# mcu.net
KiCad netlist of a schematic drawn in Altium Designer
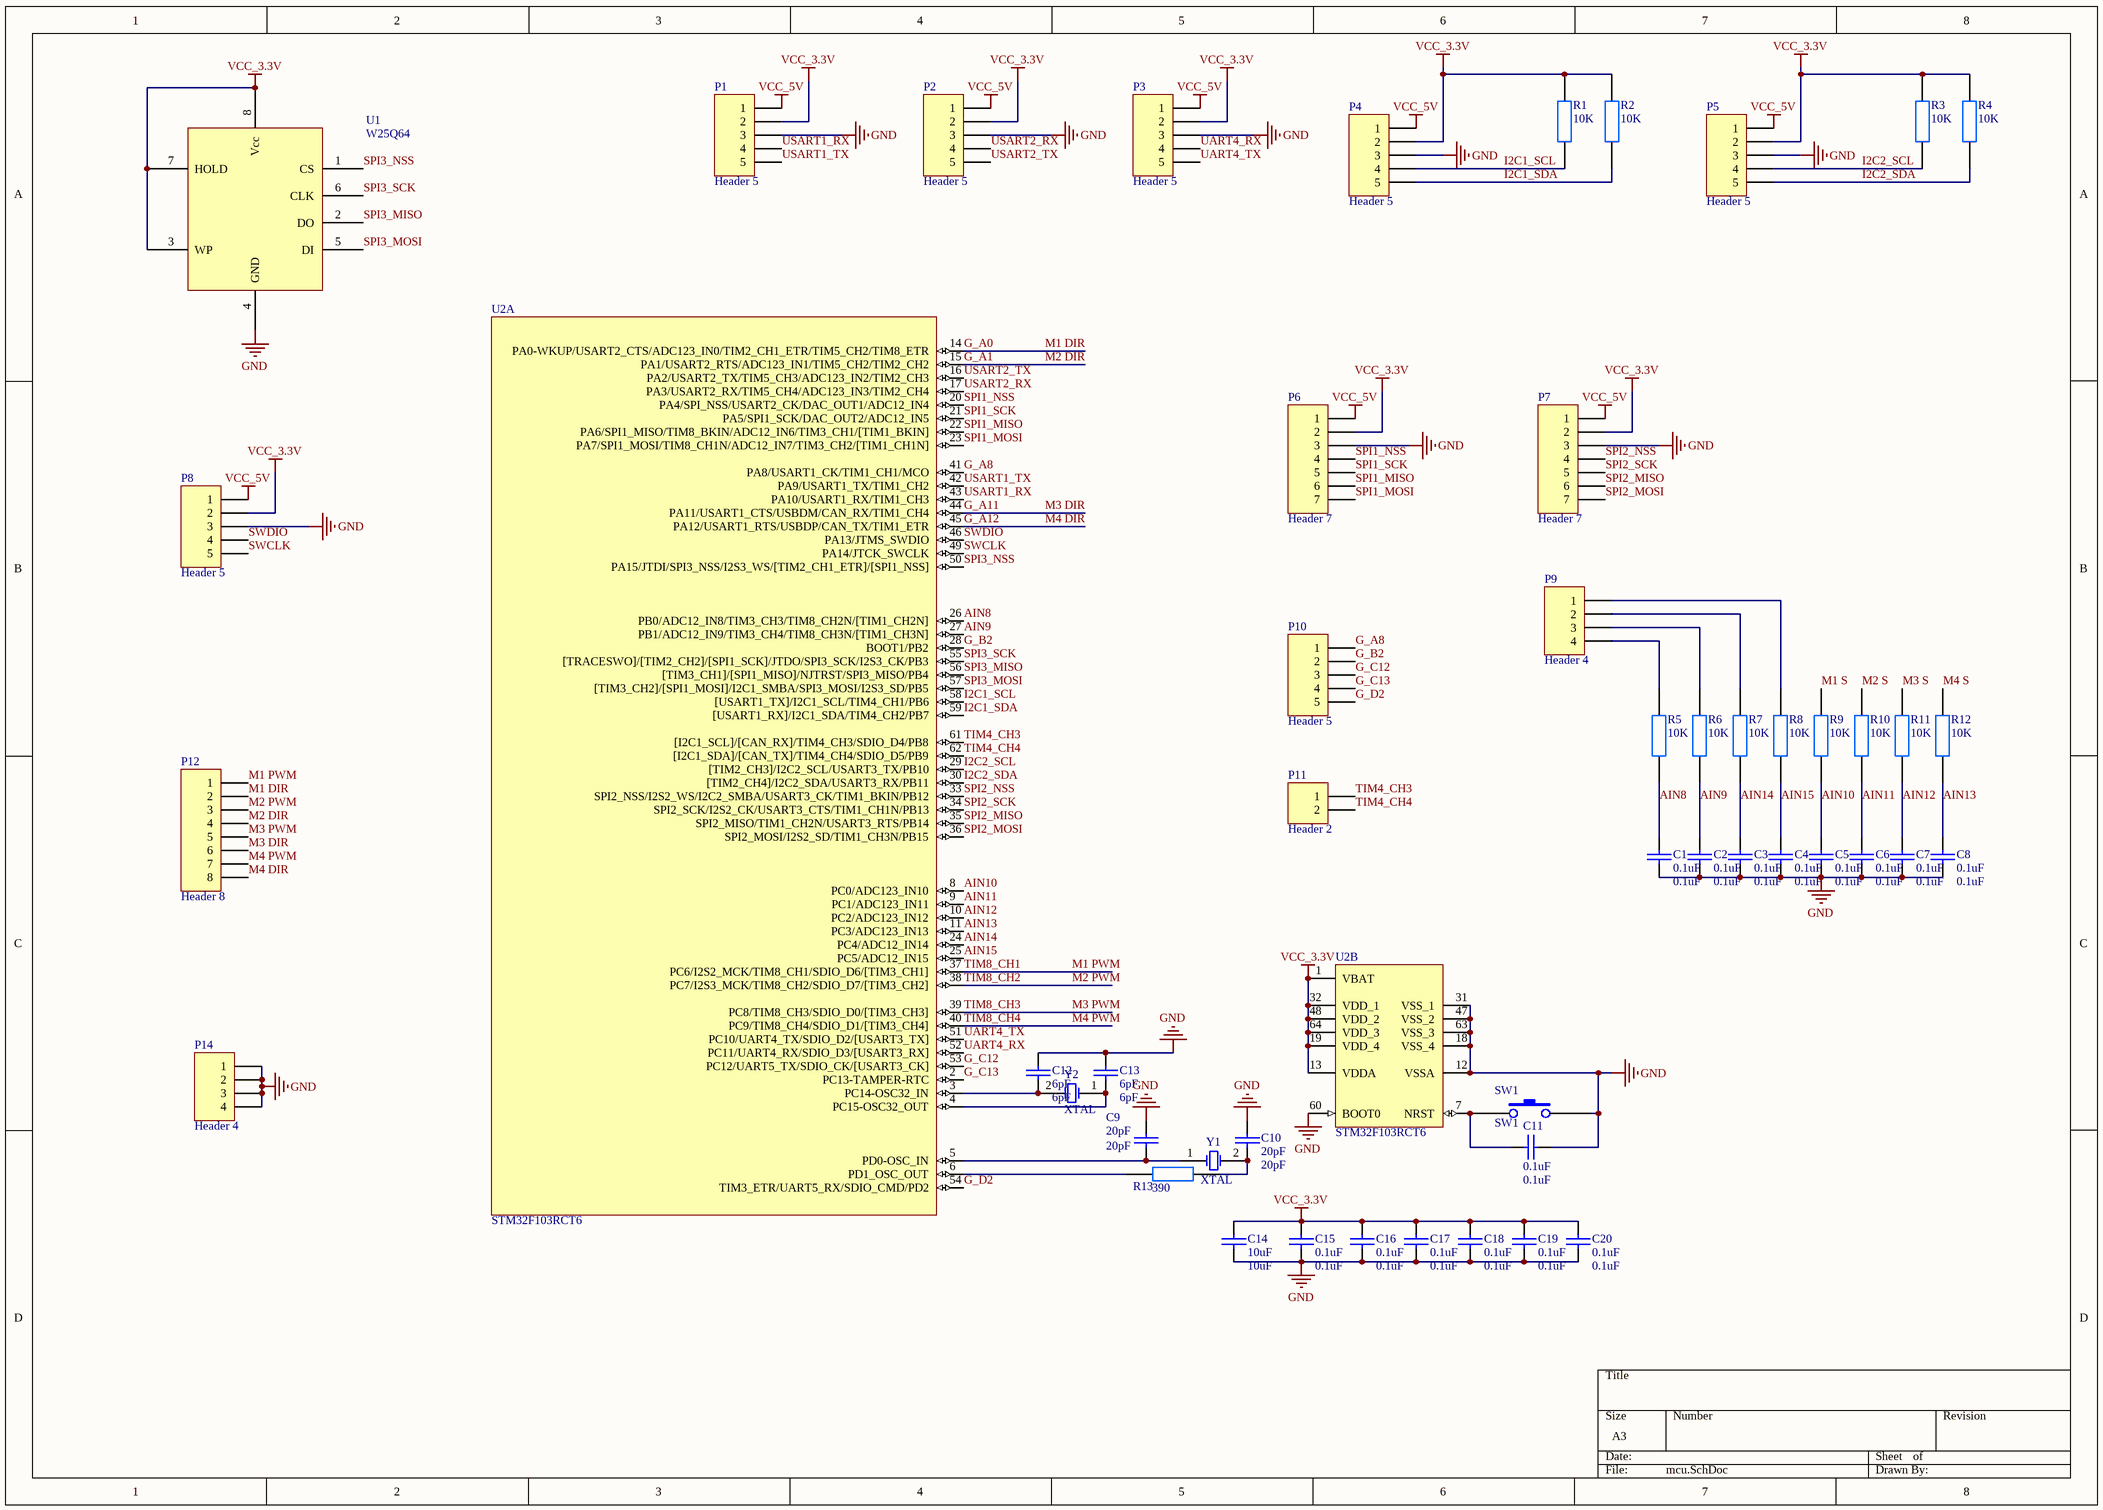
[diagram p0: mcu.SchDoc]

(export (version "E")
  (design (tool "Eeschema 10.0.6"))
  (components
    (comp (ref "C1")
      (value "0.1uF")
      (footprint "0805 CAP")
      (fields (field (name "ALTIUM_VALUE") "0.1uF"))
      (libsource (lib "common") (part "CAP"))
    )
    (comp (ref "C2")
      (value "0.1uF")
      (footprint "0805 CAP")
      (fields (field (name "ALTIUM_VALUE") "0.1uF"))
      (libsource (lib "common") (part "CAP"))
    )
    (comp (ref "C3")
      (value "0.1uF")
      (footprint "0805 CAP")
      (fields (field (name "ALTIUM_VALUE") "0.1uF"))
      (libsource (lib "common") (part "CAP"))
    )
    (comp (ref "C4")
      (value "0.1uF")
      (footprint "0805 CAP")
      (fields (field (name "ALTIUM_VALUE") "0.1uF"))
      (libsource (lib "common") (part "CAP"))
    )
    (comp (ref "C5")
      (value "0.1uF")
      (footprint "0805 CAP")
      (fields (field (name "ALTIUM_VALUE") "0.1uF"))
      (libsource (lib "common") (part "CAP"))
    )
    (comp (ref "C6")
      (value "0.1uF")
      (footprint "0805 CAP")
      (fields (field (name "ALTIUM_VALUE") "0.1uF"))
      (libsource (lib "common") (part "CAP"))
    )
    (comp (ref "C7")
      (value "0.1uF")
      (footprint "0805 CAP")
      (fields (field (name "ALTIUM_VALUE") "0.1uF"))
      (libsource (lib "common") (part "CAP"))
    )
    (comp (ref "C8")
      (value "0.1uF")
      (footprint "0805 CAP")
      (fields (field (name "ALTIUM_VALUE") "0.1uF"))
      (libsource (lib "common") (part "CAP"))
    )
    (comp (ref "C9")
      (value "20pF")
      (footprint "0805")
      (fields (field (name "ALTIUM_VALUE") "20pF"))
      (libsource (lib "common") (part "CAP"))
    )
    (comp (ref "C10")
      (value "20pF")
      (footprint "0805")
      (fields (field (name "ALTIUM_VALUE") "20pF"))
      (libsource (lib "common") (part "CAP"))
    )
    (comp (ref "C11")
      (value "0.1uF")
      (footprint "0805 CAP")
      (fields (field (name "ALTIUM_VALUE") "0.1uF"))
      (libsource (lib "common") (part "CAP"))
    )
    (comp (ref "C12")
      (value "6pF")
      (footprint "0805")
      (fields (field (name "ALTIUM_VALUE") "6pF"))
      (libsource (lib "common") (part "CAP"))
    )
    (comp (ref "C13")
      (value "6pF")
      (footprint "0805")
      (fields (field (name "ALTIUM_VALUE") "6pF"))
      (libsource (lib "common") (part "CAP"))
    )
    (comp (ref "C14")
      (value "10uF")
      (footprint "0805 CAP")
      (fields (field (name "ALTIUM_VALUE") "10uF"))
      (libsource (lib "common") (part "CAP"))
    )
    (comp (ref "C15")
      (value "0.1uF")
      (footprint "0805 CAP")
      (fields (field (name "ALTIUM_VALUE") "0.1uF"))
      (libsource (lib "common") (part "CAP"))
    )
    (comp (ref "C16")
      (value "0.1uF")
      (footprint "0805 CAP")
      (fields (field (name "ALTIUM_VALUE") "0.1uF"))
      (libsource (lib "common") (part "CAP"))
    )
    (comp (ref "C17")
      (value "0.1uF")
      (footprint "0805 CAP")
      (fields (field (name "ALTIUM_VALUE") "0.1uF"))
      (libsource (lib "common") (part "CAP"))
    )
    (comp (ref "C18")
      (value "0.1uF")
      (footprint "0805 CAP")
      (fields (field (name "ALTIUM_VALUE") "0.1uF"))
      (libsource (lib "common") (part "CAP"))
    )
    (comp (ref "C19")
      (value "0.1uF")
      (footprint "0805 CAP")
      (fields (field (name "ALTIUM_VALUE") "0.1uF"))
      (libsource (lib "common") (part "CAP"))
    )
    (comp (ref "C20")
      (value "0.1uF")
      (footprint "0805 CAP")
      (fields (field (name "ALTIUM_VALUE") "0.1uF"))
      (libsource (lib "common") (part "CAP"))
    )
    (comp (ref "P1")
      (value "Header 5")
      (footprint "sip5 i")
      (description "Header, 5-Pin")
      (fields (field (name "PUBLISHER") "Altium Limited"))
      (libsource (lib "Miscellaneous Connectors") (part "Header 5"))
    )
    (comp (ref "P2")
      (value "Header 5")
      (footprint "sip5 i")
      (description "Header, 5-Pin")
      (fields (field (name "PUBLISHER") "Altium Limited"))
      (libsource (lib "Miscellaneous Connectors") (part "Header 5"))
    )
    (comp (ref "P3")
      (value "Header 5")
      (footprint "sip5 i")
      (description "Header, 5-Pin")
      (fields (field (name "PUBLISHER") "Altium Limited"))
      (libsource (lib "Miscellaneous Connectors") (part "Header 5"))
    )
    (comp (ref "P4")
      (value "Header 5")
      (footprint "sip5 i")
      (description "Header, 5-Pin")
      (fields (field (name "PUBLISHER") "Altium Limited"))
      (libsource (lib "Miscellaneous Connectors") (part "Header 5"))
    )
    (comp (ref "P5")
      (value "Header 5")
      (footprint "sip5 i")
      (description "Header, 5-Pin")
      (fields (field (name "PUBLISHER") "Altium Limited"))
      (libsource (lib "Miscellaneous Connectors") (part "Header 5"))
    )
    (comp (ref "P6")
      (value "Header 7")
      (footprint "sip7 i")
      (description "Header, 7-Pin")
      (fields (field (name "PUBLISHER") "Altium Limited"))
      (libsource (lib "Miscellaneous Connectors") (part "Header 7"))
    )
    (comp (ref "P7")
      (value "Header 7")
      (footprint "sip7 i")
      (description "Header, 7-Pin")
      (fields (field (name "PUBLISHER") "Altium Limited"))
      (libsource (lib "Miscellaneous Connectors") (part "Header 7"))
    )
    (comp (ref "P8")
      (value "Header 5")
      (footprint "sip5 l")
      (description "Header, 5-Pin")
      (fields (field (name "PUBLISHER") "Altium Limited"))
      (libsource (lib "Miscellaneous Connectors") (part "Header 5"))
    )
    (comp (ref "P9")
      (value "Header 4")
      (footprint "sip4 i")
      (description "Header, 4-Pin")
      (fields (field (name "PUBLISHER") "Altium Limited"))
      (libsource (lib "Miscellaneous Connectors") (part "Header 4"))
    )
    (comp (ref "P10")
      (value "Header 5")
      (footprint "sip5 i")
      (description "Header, 5-Pin")
      (fields (field (name "PUBLISHER") "Altium Limited"))
      (libsource (lib "Miscellaneous Connectors") (part "Header 5"))
    )
    (comp (ref "P11")
      (value "Header 2")
      (footprint "sip2 i")
      (description "Header, 2-Pin")
      (fields (field (name "PUBLISHER") "Altium Limited"))
      (libsource (lib "Miscellaneous Connectors") (part "Header 2"))
    )
    (comp (ref "P12")
      (value "Header 8")
      (footprint "sip8 i")
      (description "Header, 8-Pin")
      (fields (field (name "PUBLISHER") "Altium Limited"))
      (libsource (lib "Miscellaneous Connectors") (part "Header 8"))
    )
    (comp (ref "P14")
      (value "Header 4")
      (footprint "sip4 i")
      (description "Header, 4-Pin")
      (fields (field (name "PUBLISHER") "Altium Limited"))
      (libsource (lib "Miscellaneous Connectors") (part "Header 4"))
    )
    (comp (ref "R1")
      (value "10K")
      (footprint "0805")
      (description "RES")
      (libsource (lib "common") (part "RES"))
    )
    (comp (ref "R2")
      (value "10K")
      (footprint "0805")
      (description "RES")
      (libsource (lib "common") (part "RES"))
    )
    (comp (ref "R3")
      (value "10K")
      (footprint "0805")
      (description "RES")
      (libsource (lib "common") (part "RES"))
    )
    (comp (ref "R4")
      (value "10K")
      (footprint "0805")
      (description "RES")
      (libsource (lib "common") (part "RES"))
    )
    (comp (ref "R5")
      (value "10K")
      (footprint "0805")
      (description "RES")
      (libsource (lib "common") (part "RES"))
    )
    (comp (ref "R6")
      (value "10K")
      (footprint "0805")
      (description "RES")
      (libsource (lib "common") (part "RES"))
    )
    (comp (ref "R7")
      (value "10K")
      (footprint "0805")
      (description "RES")
      (libsource (lib "common") (part "RES"))
    )
    (comp (ref "R8")
      (value "10K")
      (footprint "0805")
      (description "RES")
      (libsource (lib "common") (part "RES"))
    )
    (comp (ref "R9")
      (value "10K")
      (footprint "0805")
      (description "RES")
      (libsource (lib "common") (part "RES"))
    )
    (comp (ref "R10")
      (value "10K")
      (footprint "0805")
      (description "RES")
      (libsource (lib "common") (part "RES"))
    )
    (comp (ref "R11")
      (value "10K")
      (footprint "0805")
      (description "RES")
      (libsource (lib "common") (part "RES"))
    )
    (comp (ref "R12")
      (value "10K")
      (footprint "0805")
      (description "RES")
      (libsource (lib "common") (part "RES"))
    )
    (comp (ref "R13")
      (value "390")
      (footprint "0805")
      (description "RES")
      (libsource (lib "common") (part "RES"))
    )
    (comp (ref "SW1") (value "SW1") (footprint "KEYA SMT") (libsource (lib "common") (part "SW1")))
    (comp (ref "U1") (value "W25Q64") (footprint "so-8 fat") (libsource (lib "common") (part "W25Q64")))
    (comp (ref "U2")
      (value "STM32F103RCT6")
      (footprint "QFP64")
      (libsource (lib "common") (part "STM32F103RCT6"))
    )
    (comp (ref "Y1")
      (value "XTAL")
      (footprint "XTAL SOT")
      (description "Crystal Oscillator")
      (fields (field (name "PUBLISHER") "Altium Limited"))
      (libsource (lib "common") (part "XTAL"))
    )
    (comp (ref "Y2")
      (value "XTAL")
      (footprint "xtal 26")
      (description "Crystal Oscillator")
      (fields (field (name "PUBLISHER") "Altium Limited"))
      (libsource (lib "common") (part "XTAL"))
    )
  )
  (nets
    (net (code "1") (name "/AIN8") (class "Default")
      (node (ref "C1") (pin "1") (pinfunction "1_1") (pintype "passive"))
      (node (ref "R5") (pin "1") (pinfunction "1_1") (pintype "passive"))
      (node (ref "U2") (pin "26") (pinfunction "PB0/ADC12_IN8/TIM3_CH3/TIM8_CH2N/[TIM1_CH2N]_26") (pintype "bidirectional"))
    )
    (net (code "2") (name "/AIN9") (class "Default")
      (node (ref "C2") (pin "1") (pinfunction "1_1") (pintype "passive"))
      (node (ref "R6") (pin "1") (pinfunction "1_1") (pintype "passive"))
      (node (ref "U2") (pin "27") (pinfunction "PB1/ADC12_IN9/TIM3_CH4/TIM8_CH3N/[TIM1_CH3N]_27") (pintype "bidirectional"))
    )
    (net (code "3") (name "/AIN10") (class "Default")
      (node (ref "C5") (pin "1") (pinfunction "1_1") (pintype "passive"))
      (node (ref "R9") (pin "1") (pinfunction "1_1") (pintype "passive"))
      (node (ref "U2") (pin "8") (pinfunction "PC0/ADC123_IN10_8") (pintype "bidirectional"))
    )
    (net (code "4") (name "/AIN11") (class "Default")
      (node (ref "C6") (pin "1") (pinfunction "1_1") (pintype "passive"))
      (node (ref "R10") (pin "1") (pinfunction "1_1") (pintype "passive"))
      (node (ref "U2") (pin "9") (pinfunction "PC1/ADC123_IN11_9") (pintype "bidirectional"))
    )
    (net (code "5") (name "/AIN12") (class "Default")
      (node (ref "C7") (pin "1") (pinfunction "1_1") (pintype "passive"))
      (node (ref "R11") (pin "1") (pinfunction "1_1") (pintype "passive"))
      (node (ref "U2") (pin "10") (pinfunction "PC2/ADC123_IN12_10") (pintype "bidirectional"))
    )
    (net (code "6") (name "/AIN13") (class "Default")
      (node (ref "C8") (pin "1") (pinfunction "1_1") (pintype "passive"))
      (node (ref "R12") (pin "1") (pinfunction "1_1") (pintype "passive"))
      (node (ref "U2") (pin "11") (pinfunction "PC3/ADC123_IN13_11") (pintype "bidirectional"))
    )
    (net (code "7") (name "/AIN14") (class "Default")
      (node (ref "C3") (pin "1") (pinfunction "1_1") (pintype "passive"))
      (node (ref "R7") (pin "1") (pinfunction "1_1") (pintype "passive"))
      (node (ref "U2") (pin "24") (pinfunction "PC4/ADC12_IN14_24") (pintype "bidirectional"))
    )
    (net (code "8") (name "/AIN15") (class "Default")
      (node (ref "C4") (pin "1") (pinfunction "1_1") (pintype "passive"))
      (node (ref "R8") (pin "1") (pinfunction "1_1") (pintype "passive"))
      (node (ref "U2") (pin "25") (pinfunction "PC5/ADC12_IN15_25") (pintype "bidirectional"))
    )
    (net (code "9") (name "/G_A0") (class "Default")
      (node (ref "P12") (pin "2") (pinfunction "2_2") (pintype "passive"))
      (node (ref "U2") (pin "14") (pinfunction "PA0-WKUP/USART2_CTS/ADC123_IN0/TIM2_CH1_ETR/TIM5_CH2/TIM8_ETR_14") (pintype "bidirectional"))
    )
    (net (code "10") (name "/G_A1") (class "Default")
      (node (ref "P12") (pin "4") (pinfunction "4_4") (pintype "passive"))
      (node (ref "U2") (pin "15") (pinfunction "PA1/USART2_RTS/ADC123_IN1/TIM5_CH2/TIM2_CH2_15") (pintype "bidirectional"))
    )
    (net (code "11") (name "/G_A8") (class "Default")
      (node (ref "P10") (pin "1") (pinfunction "1_1") (pintype "passive"))
      (node (ref "U2") (pin "41") (pinfunction "PA8/USART1_CK/TIM1_CH1/MCO_41") (pintype "bidirectional"))
    )
    (net (code "12") (name "/G_A11") (class "Default")
      (node (ref "P12") (pin "6") (pinfunction "6_6") (pintype "passive"))
      (node (ref "U2") (pin "44") (pinfunction "PA11/USART1_CTS/USBDM/CAN_RX/TIM1_CH4_44") (pintype "bidirectional"))
    )
    (net (code "13") (name "/G_A12") (class "Default")
      (node (ref "P12") (pin "8") (pinfunction "8_8") (pintype "passive"))
      (node (ref "U2") (pin "45") (pinfunction "PA12/USART1_RTS/USBDP/CAN_TX/TIM1_ETR_45") (pintype "bidirectional"))
    )
    (net (code "14") (name "/G_B2") (class "Default")
      (node (ref "P10") (pin "2") (pinfunction "2_2") (pintype "passive"))
      (node (ref "U2") (pin "28") (pinfunction "BOOT1/PB2_28") (pintype "bidirectional"))
    )
    (net (code "15") (name "/G_C12") (class "Default")
      (node (ref "P10") (pin "3") (pinfunction "3_3") (pintype "passive"))
      (node (ref "U2") (pin "53") (pinfunction "PC12/UART5_TX/SDIO_CK/[USART3_CK]_53") (pintype "bidirectional"))
    )
    (net (code "16") (name "/G_C13") (class "Default")
      (node (ref "P10") (pin "4") (pinfunction "4_4") (pintype "passive"))
      (node (ref "U2") (pin "2") (pinfunction "PC13-TAMPER-RTC_2") (pintype "bidirectional"))
    )
    (net (code "17") (name "/G_D2") (class "Default")
      (node (ref "P10") (pin "5") (pinfunction "5_5") (pintype "passive"))
      (node (ref "U2") (pin "54") (pinfunction "TIM3_ETR/UART5_RX/SDIO_CMD/PD2_54") (pintype "bidirectional"))
    )
    (net (code "18") (name "/I2C1_SCL") (class "Default")
      (node (ref "P4") (pin "4") (pinfunction "4_4") (pintype "passive"))
      (node (ref "R1") (pin "1") (pinfunction "1_1") (pintype "passive"))
      (node (ref "U2") (pin "58") (pinfunction "[USART1_TX]/I2C1_SCL/TIM4_CH1/PB6_58") (pintype "bidirectional"))
    )
    (net (code "19") (name "/I2C1_SDA") (class "Default")
      (node (ref "P4") (pin "5") (pinfunction "5_5") (pintype "passive"))
      (node (ref "R2") (pin "1") (pinfunction "1_1") (pintype "passive"))
      (node (ref "U2") (pin "59") (pinfunction "[USART1_RX]/I2C1_SDA/TIM4_CH2/PB7_59") (pintype "bidirectional"))
    )
    (net (code "20") (name "/I2C2_SCL") (class "Default")
      (node (ref "P5") (pin "4") (pinfunction "4_4") (pintype "passive"))
      (node (ref "R3") (pin "1") (pinfunction "1_1") (pintype "passive"))
      (node (ref "U2") (pin "29") (pinfunction "[TIM2_CH3]/I2C2_SCL/USART3_TX/PB10_29") (pintype "bidirectional"))
    )
    (net (code "21") (name "/I2C2_SDA") (class "Default")
      (node (ref "P5") (pin "5") (pinfunction "5_5") (pintype "passive"))
      (node (ref "R4") (pin "1") (pinfunction "1_1") (pintype "passive"))
      (node (ref "U2") (pin "30") (pinfunction "[TIM2_CH4]/I2C2_SDA/USART3_RX/PB11_30") (pintype "bidirectional"))
    )
    (net (code "22") (name "/M1 PWM") (class "Default")
      (node (ref "P12") (pin "1") (pinfunction "1_1") (pintype "passive"))
      (node (ref "U2") (pin "37") (pinfunction "PC6/I2S2_MCK/TIM8_CH1/SDIO_D6/[TIM3_CH1]_37") (pintype "bidirectional"))
    )
    (net (code "23") (name "/M1 S") (class "Default")
      (node (ref "R9") (pin "2") (pinfunction "2_2") (pintype "passive"))
    )
    (net (code "24") (name "/M2 PWM") (class "Default")
      (node (ref "P12") (pin "3") (pinfunction "3_3") (pintype "passive"))
      (node (ref "U2") (pin "38") (pinfunction "PC7/I2S3_MCK/TIM8_CH2/SDIO_D7/[TIM3_CH2]_38") (pintype "bidirectional"))
    )
    (net (code "25") (name "/M2 S") (class "Default")
      (node (ref "R10") (pin "2") (pinfunction "2_2") (pintype "passive"))
    )
    (net (code "26") (name "/M3 PWM") (class "Default")
      (node (ref "P12") (pin "5") (pinfunction "5_5") (pintype "passive"))
      (node (ref "U2") (pin "39") (pinfunction "PC8/TIM8_CH3/SDIO_D0/[TIM3_CH3]_39") (pintype "bidirectional"))
    )
    (net (code "27") (name "/M3 S") (class "Default")
      (node (ref "R11") (pin "2") (pinfunction "2_2") (pintype "passive"))
    )
    (net (code "28") (name "/M4 PWM") (class "Default")
      (node (ref "P12") (pin "7") (pinfunction "7_7") (pintype "passive"))
      (node (ref "U2") (pin "40") (pinfunction "PC9/TIM8_CH4/SDIO_D1/[TIM3_CH4]_40") (pintype "bidirectional"))
    )
    (net (code "29") (name "/M4 S") (class "Default")
      (node (ref "R12") (pin "2") (pinfunction "2_2") (pintype "passive"))
    )
    (net (code "30") (name "/SPI1_MISO") (class "Default")
      (node (ref "P6") (pin "6") (pinfunction "6_6") (pintype "passive"))
      (node (ref "U2") (pin "22") (pinfunction "PA6/SPI1_MISO/TIM8_BKIN/ADC12_IN6/TIM3_CH1/[TIM1_BKIN]_22") (pintype "bidirectional"))
    )
    (net (code "31") (name "/SPI1_MOSI") (class "Default")
      (node (ref "P6") (pin "7") (pinfunction "7_7") (pintype "passive"))
      (node (ref "U2") (pin "23") (pinfunction "PA7/SPI1_MOSI/TIM8_CH1N/ADC12_IN7/TIM3_CH2/[TIM1_CH1N]_23") (pintype "bidirectional"))
    )
    (net (code "32") (name "/SPI1_NSS") (class "Default")
      (node (ref "P6") (pin "4") (pinfunction "4_4") (pintype "passive"))
      (node (ref "U2") (pin "20") (pinfunction "PA4/SPI_NSS/USART2_CK/DAC_OUT1/ADC12_IN4_20") (pintype "bidirectional"))
    )
    (net (code "33") (name "/SPI1_SCK") (class "Default")
      (node (ref "P6") (pin "5") (pinfunction "5_5") (pintype "passive"))
      (node (ref "U2") (pin "21") (pinfunction "PA5/SPI1_SCK/DAC_OUT2/ADC12_IN5_21") (pintype "bidirectional"))
    )
    (net (code "34") (name "/SPI2_MISO") (class "Default")
      (node (ref "P7") (pin "6") (pinfunction "6_6") (pintype "passive"))
      (node (ref "U2") (pin "35") (pinfunction "SPI2_MISO/TIM1_CH2N/USART3_RTS/PB14_35") (pintype "bidirectional"))
    )
    (net (code "35") (name "/SPI2_MOSI") (class "Default")
      (node (ref "P7") (pin "7") (pinfunction "7_7") (pintype "passive"))
      (node (ref "U2") (pin "36") (pinfunction "SPI2_MOSI/I2S2_SD/TIM1_CH3N/PB15_36") (pintype "bidirectional"))
    )
    (net (code "36") (name "/SPI2_NSS") (class "Default")
      (node (ref "P7") (pin "4") (pinfunction "4_4") (pintype "passive"))
      (node (ref "U2") (pin "33") (pinfunction "SPI2_NSS/I2S2_WS/I2C2_SMBA/USART3_CK/TIM1_BKIN/PB12_33") (pintype "bidirectional"))
    )
    (net (code "37") (name "/SPI2_SCK") (class "Default")
      (node (ref "P7") (pin "5") (pinfunction "5_5") (pintype "passive"))
      (node (ref "U2") (pin "34") (pinfunction "SPI2_SCK/I2S2_CK/USART3_CTS/TIM1_CH1N/PB13_34") (pintype "bidirectional"))
    )
    (net (code "38") (name "/SPI3_MISO") (class "Default")
      (node (ref "U1") (pin "2") (pinfunction "DO_2") (pintype "passive"))
      (node (ref "U2") (pin "56") (pinfunction "[TIM3_CH1]/[SPI1_MISO]/NJTRST/SPI3_MISO/PB4_56") (pintype "bidirectional"))
    )
    (net (code "39") (name "/SPI3_MOSI") (class "Default")
      (node (ref "U1") (pin "5") (pinfunction "DI_5") (pintype "passive"))
      (node (ref "U2") (pin "57") (pinfunction "[TIM3_CH2]/[SPI1_MOSI]/I2C1_SMBA/SPI3_MOSI/I2S3_SD/PB5_57") (pintype "bidirectional"))
    )
    (net (code "40") (name "/SPI3_NSS") (class "Default")
      (node (ref "U1") (pin "1") (pinfunction "CS_1") (pintype "passive"))
      (node (ref "U2") (pin "50") (pinfunction "PA15/JTDI/SPI3_NSS/I2S3_WS/[TIM2_CH1_ETR]/[SPI1_NSS]_50") (pintype "bidirectional"))
    )
    (net (code "41") (name "/SPI3_SCK") (class "Default")
      (node (ref "U1") (pin "6") (pinfunction "CLK_6") (pintype "passive"))
      (node (ref "U2") (pin "55") (pinfunction "[TRACESWO]/[TIM2_CH2]/[SPI1_SCK]/JTDO/SPI3_SCK/I2S3_CK/PB3_55") (pintype "bidirectional"))
    )
    (net (code "42") (name "/SWCLK") (class "Default")
      (node (ref "P8") (pin "5") (pinfunction "5_5") (pintype "passive"))
      (node (ref "U2") (pin "49") (pinfunction "PA14/JTCK_SWCLK_49") (pintype "bidirectional"))
    )
    (net (code "43") (name "/SWDIO") (class "Default")
      (node (ref "P8") (pin "4") (pinfunction "4_4") (pintype "passive"))
      (node (ref "U2") (pin "46") (pinfunction "PA13/JTMS_SWDIO_46") (pintype "bidirectional"))
    )
    (net (code "44") (name "/TIM4_CH3") (class "Default")
      (node (ref "P11") (pin "1") (pinfunction "1_1") (pintype "passive"))
      (node (ref "U2") (pin "61") (pinfunction "[I2C1_SCL]/[CAN_RX]/TIM4_CH3/SDIO_D4/PB8_61") (pintype "bidirectional"))
    )
    (net (code "45") (name "/TIM4_CH4") (class "Default")
      (node (ref "P11") (pin "2") (pinfunction "2_2") (pintype "passive"))
      (node (ref "U2") (pin "62") (pinfunction "[I2C1_SDA]/[CAN_TX]/TIM4_CH4/SDIO_D5/PB9_62") (pintype "bidirectional"))
    )
    (net (code "46") (name "/UART4_RX") (class "Default")
      (node (ref "P3") (pin "4") (pinfunction "4_4") (pintype "passive"))
      (node (ref "U2") (pin "52") (pinfunction "PC11/UART4_RX/SDIO_D3/[USART3_RX]_52") (pintype "bidirectional"))
    )
    (net (code "47") (name "/UART4_TX") (class "Default")
      (node (ref "P3") (pin "5") (pinfunction "5_5") (pintype "passive"))
      (node (ref "U2") (pin "51") (pinfunction "PC10/UART4_TX/SDIO_D2/[USART3_TX]_51") (pintype "bidirectional"))
    )
    (net (code "48") (name "/USART1_RX") (class "Default")
      (node (ref "P1") (pin "4") (pinfunction "4_4") (pintype "passive"))
      (node (ref "U2") (pin "43") (pinfunction "PA10/USART1_RX/TIM1_CH3_43") (pintype "bidirectional"))
    )
    (net (code "49") (name "/USART1_TX") (class "Default")
      (node (ref "P1") (pin "5") (pinfunction "5_5") (pintype "passive"))
      (node (ref "U2") (pin "42") (pinfunction "PA9/USART1_TX/TIM1_CH2_42") (pintype "bidirectional"))
    )
    (net (code "50") (name "/USART2_RX") (class "Default")
      (node (ref "P2") (pin "4") (pinfunction "4_4") (pintype "passive"))
      (node (ref "U2") (pin "17") (pinfunction "PA3/USART2_RX/TIM5_CH4/ADC123_IN3/TIM2_CH4_17") (pintype "bidirectional"))
    )
    (net (code "51") (name "/USART2_TX") (class "Default")
      (node (ref "P2") (pin "5") (pinfunction "5_5") (pintype "passive"))
      (node (ref "U2") (pin "16") (pinfunction "PA2/USART2_TX/TIM5_CH3/ADC123_IN2/TIM2_CH3_16") (pintype "bidirectional"))
    )
    (net (code "52") (name "GND") (class "Default")
      (node (ref "C1") (pin "2") (pinfunction "2_2") (pintype "passive"))
      (node (ref "C10") (pin "2") (pinfunction "2_2") (pintype "passive"))
      (node (ref "C11") (pin "2") (pinfunction "2_2") (pintype "passive"))
      (node (ref "C12") (pin "2") (pinfunction "2_2") (pintype "passive"))
      (node (ref "C13") (pin "2") (pinfunction "2_2") (pintype "passive"))
      (node (ref "C14") (pin "1") (pinfunction "1_1") (pintype "passive"))
      (node (ref "C15") (pin "1") (pinfunction "1_1") (pintype "passive"))
      (node (ref "C16") (pin "1") (pinfunction "1_1") (pintype "passive"))
      (node (ref "C17") (pin "1") (pinfunction "1_1") (pintype "passive"))
      (node (ref "C18") (pin "1") (pinfunction "1_1") (pintype "passive"))
      (node (ref "C19") (pin "1") (pinfunction "1_1") (pintype "passive"))
      (node (ref "C2") (pin "2") (pinfunction "2_2") (pintype "passive"))
      (node (ref "C20") (pin "1") (pinfunction "1_1") (pintype "passive"))
      (node (ref "C3") (pin "2") (pinfunction "2_2") (pintype "passive"))
      (node (ref "C4") (pin "2") (pinfunction "2_2") (pintype "passive"))
      (node (ref "C5") (pin "2") (pinfunction "2_2") (pintype "passive"))
      (node (ref "C6") (pin "2") (pinfunction "2_2") (pintype "passive"))
      (node (ref "C7") (pin "2") (pinfunction "2_2") (pintype "passive"))
      (node (ref "C8") (pin "2") (pinfunction "2_2") (pintype "passive"))
      (node (ref "C9") (pin "2") (pinfunction "2_2") (pintype "passive"))
      (node (ref "P1") (pin "3") (pinfunction "3_3") (pintype "passive"))
      (node (ref "P14") (pin "1") (pinfunction "1_1") (pintype "passive"))
      (node (ref "P14") (pin "2") (pinfunction "2_2") (pintype "passive"))
      (node (ref "P14") (pin "3") (pinfunction "3_3") (pintype "passive"))
      (node (ref "P14") (pin "4") (pinfunction "4_4") (pintype "passive"))
      (node (ref "P2") (pin "3") (pinfunction "3_3") (pintype "passive"))
      (node (ref "P3") (pin "3") (pinfunction "3_3") (pintype "passive"))
      (node (ref "P4") (pin "3") (pinfunction "3_3") (pintype "passive"))
      (node (ref "P5") (pin "3") (pinfunction "3_3") (pintype "passive"))
      (node (ref "P6") (pin "3") (pinfunction "3_3") (pintype "passive"))
      (node (ref "P7") (pin "3") (pinfunction "3_3") (pintype "passive"))
      (node (ref "P8") (pin "3") (pinfunction "3_3") (pintype "passive"))
      (node (ref "SW1") (pin "2") (pinfunction "2_2") (pintype "passive"))
      (node (ref "U1") (pin "4") (pinfunction "GND_4") (pintype "passive"))
      (node (ref "U2") (pin "12") (pinfunction "VSSA_12") (pintype "power_in"))
      (node (ref "U2") (pin "18") (pinfunction "VSS_4_18") (pintype "power_in"))
      (node (ref "U2") (pin "31") (pinfunction "VSS_1_31") (pintype "power_in"))
      (node (ref "U2") (pin "47") (pinfunction "VSS_2_47") (pintype "power_in"))
      (node (ref "U2") (pin "60") (pinfunction "BOOT0_60") (pintype "input"))
      (node (ref "U2") (pin "63") (pinfunction "VSS_3_63") (pintype "power_in"))
    )
    (net (code "53") (name "Net-(P9-Pad1)") (class "Default")
      (node (ref "P9") (pin "1") (pinfunction "1_1") (pintype "passive"))
      (node (ref "R8") (pin "2") (pinfunction "2_2") (pintype "passive"))
    )
    (net (code "54") (name "Net-(P9-Pad2)") (class "Default")
      (node (ref "P9") (pin "2") (pinfunction "2_2") (pintype "passive"))
      (node (ref "R7") (pin "2") (pinfunction "2_2") (pintype "passive"))
    )
    (net (code "55") (name "Net-(P9-Pad3)") (class "Default")
      (node (ref "P9") (pin "3") (pinfunction "3_3") (pintype "passive"))
      (node (ref "R6") (pin "2") (pinfunction "2_2") (pintype "passive"))
    )
    (net (code "56") (name "Net-(P9-Pad4)") (class "Default")
      (node (ref "P9") (pin "4") (pinfunction "4_4") (pintype "passive"))
      (node (ref "R5") (pin "2") (pinfunction "2_2") (pintype "passive"))
    )
    (net (code "57") (name "Net-(U2A-PC14-OSC32_IN)") (class "Default")
      (node (ref "C12") (pin "1") (pinfunction "1_1") (pintype "passive"))
      (node (ref "U2") (pin "3") (pinfunction "PC14-OSC32_IN_3") (pintype "bidirectional"))
      (node (ref "Y2") (pin "2") (pinfunction "OSC2_2") (pintype "passive"))
    )
    (net (code "58") (name "Net-(U2A-PC15-OSC32_OUT)") (class "Default")
      (node (ref "C13") (pin "1") (pinfunction "1_1") (pintype "passive"))
      (node (ref "U2") (pin "4") (pinfunction "PC15-OSC32_OUT_4") (pintype "bidirectional"))
      (node (ref "Y2") (pin "1") (pinfunction "OSC1_1") (pintype "passive"))
    )
    (net (code "59") (name "Net-(U2A-PD0-OSC_IN)") (class "Default")
      (node (ref "C9") (pin "1") (pinfunction "1_1") (pintype "passive"))
      (node (ref "U2") (pin "5") (pinfunction "PD0-OSC_IN_5") (pintype "bidirectional"))
      (node (ref "Y1") (pin "1") (pinfunction "OSC1_1") (pintype "passive"))
    )
    (net (code "60") (name "Net-(U2A-PD1_OSC_OUT)") (class "Default")
      (node (ref "R13") (pin "1") (pinfunction "1_1") (pintype "passive"))
      (node (ref "U2") (pin "6") (pinfunction "PD1_OSC_OUT_6") (pintype "bidirectional"))
    )
    (net (code "61") (name "Net-(U2B-NRST)") (class "Default")
      (node (ref "C11") (pin "1") (pinfunction "1_1") (pintype "passive"))
      (node (ref "SW1") (pin "1") (pinfunction "1_1") (pintype "passive"))
      (node (ref "U2") (pin "7") (pinfunction "NRST_7") (pintype "bidirectional"))
    )
    (net (code "62") (name "Net-(Y1-OSC2)") (class "Default")
      (node (ref "C10") (pin "1") (pinfunction "1_1") (pintype "passive"))
      (node (ref "R13") (pin "2") (pinfunction "2_2") (pintype "passive"))
      (node (ref "Y1") (pin "2") (pinfunction "OSC2_2") (pintype "passive"))
    )
    (net (code "63") (name "VCC_3.3V") (class "Default")
      (node (ref "C14") (pin "2") (pinfunction "2_2") (pintype "passive"))
      (node (ref "C15") (pin "2") (pinfunction "2_2") (pintype "passive"))
      (node (ref "C16") (pin "2") (pinfunction "2_2") (pintype "passive"))
      (node (ref "C17") (pin "2") (pinfunction "2_2") (pintype "passive"))
      (node (ref "C18") (pin "2") (pinfunction "2_2") (pintype "passive"))
      (node (ref "C19") (pin "2") (pinfunction "2_2") (pintype "passive"))
      (node (ref "C20") (pin "2") (pinfunction "2_2") (pintype "passive"))
      (node (ref "P1") (pin "2") (pinfunction "2_2") (pintype "passive"))
      (node (ref "P2") (pin "2") (pinfunction "2_2") (pintype "passive"))
      (node (ref "P3") (pin "2") (pinfunction "2_2") (pintype "passive"))
      (node (ref "P4") (pin "2") (pinfunction "2_2") (pintype "passive"))
      (node (ref "P5") (pin "2") (pinfunction "2_2") (pintype "passive"))
      (node (ref "P6") (pin "2") (pinfunction "2_2") (pintype "passive"))
      (node (ref "P7") (pin "2") (pinfunction "2_2") (pintype "passive"))
      (node (ref "P8") (pin "2") (pinfunction "2_2") (pintype "passive"))
      (node (ref "R1") (pin "2") (pinfunction "2_2") (pintype "passive"))
      (node (ref "R2") (pin "2") (pinfunction "2_2") (pintype "passive"))
      (node (ref "R3") (pin "2") (pinfunction "2_2") (pintype "passive"))
      (node (ref "R4") (pin "2") (pinfunction "2_2") (pintype "passive"))
      (node (ref "U1") (pin "3") (pinfunction "WP_3") (pintype "passive"))
      (node (ref "U1") (pin "7") (pinfunction "HOLD_7") (pintype "passive"))
      (node (ref "U1") (pin "8") (pinfunction "Vcc_8") (pintype "passive"))
      (node (ref "U2") (pin "1") (pinfunction "VBAT_1") (pintype "power_in"))
      (node (ref "U2") (pin "13") (pinfunction "VDDA_13") (pintype "power_in"))
      (node (ref "U2") (pin "19") (pinfunction "VDD_4_19") (pintype "power_in"))
      (node (ref "U2") (pin "32") (pinfunction "VDD_1_32") (pintype "power_in"))
      (node (ref "U2") (pin "48") (pinfunction "VDD_2_48") (pintype "power_in"))
      (node (ref "U2") (pin "64") (pinfunction "VDD_3_64") (pintype "power_in"))
    )
    (net (code "64") (name "VCC_5V") (class "Default")
      (node (ref "P1") (pin "1") (pinfunction "1_1") (pintype "passive"))
      (node (ref "P2") (pin "1") (pinfunction "1_1") (pintype "passive"))
      (node (ref "P3") (pin "1") (pinfunction "1_1") (pintype "passive"))
      (node (ref "P4") (pin "1") (pinfunction "1_1") (pintype "passive"))
      (node (ref "P5") (pin "1") (pinfunction "1_1") (pintype "passive"))
      (node (ref "P6") (pin "1") (pinfunction "1_1") (pintype "passive"))
      (node (ref "P7") (pin "1") (pinfunction "1_1") (pintype "passive"))
      (node (ref "P8") (pin "1") (pinfunction "1_1") (pintype "passive"))
    )
  )
)
